# CTRL.net
KiCad netlist of a schematic drawn in Altium Designer
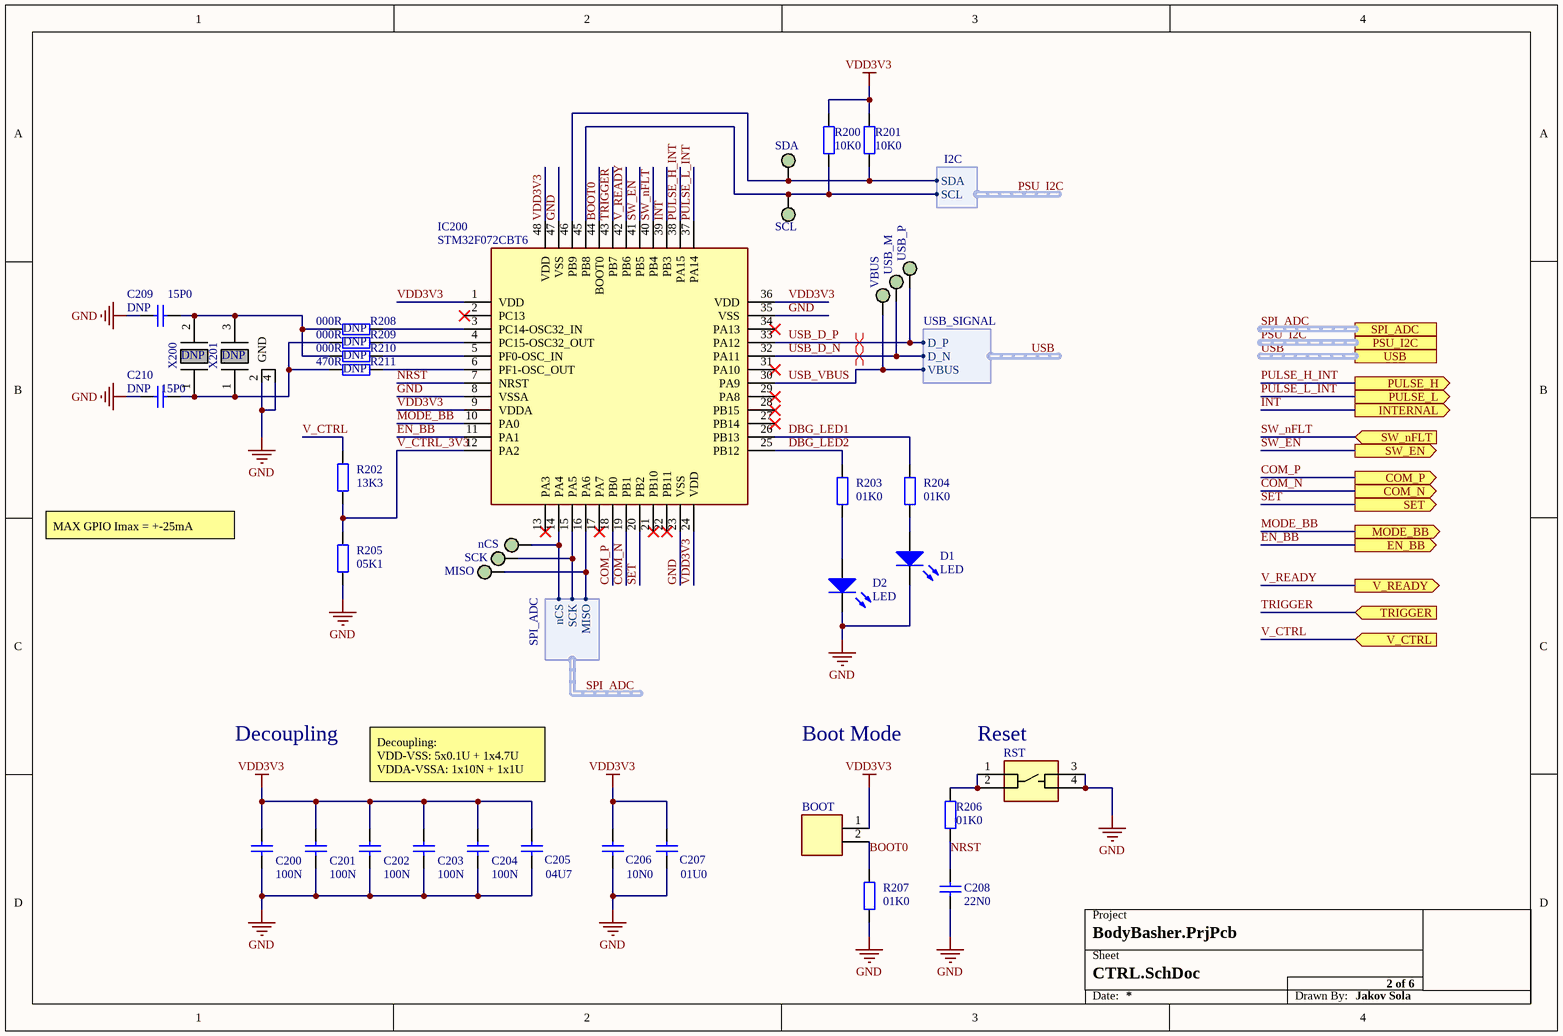
[diagram p0: CTRL.SchDoc]

(export (version "E")
  (design (tool "Eeschema 10.0.6"))
  (components
    (comp (ref "BOOT")
      (value "CON_2P")
      (footprint "2MMHBS02VT02HTB")
      (libsource (lib "Other_passive") (part "CON_2P"))
    )
    (comp (ref "C200")
      (value "Cap")
      (footprint "CAPC0603N")
      (fields
        (field (name "VALUE_4C") "100N")
        (field (name "VOLTAGE") "25V")
        (field (name "TOLERANCE") "0.1")
      )
      (libsource (lib "Capacitors") (part "Cap"))
    )
    (comp (ref "C201")
      (value "Cap")
      (footprint "CAPC0603N")
      (fields
        (field (name "VALUE_4C") "100N")
        (field (name "VOLTAGE") "25V")
        (field (name "TOLERANCE") "0.1")
      )
      (libsource (lib "Capacitors") (part "Cap"))
    )
    (comp (ref "C202")
      (value "Cap")
      (footprint "CAPC0603N")
      (fields
        (field (name "VALUE_4C") "100N")
        (field (name "VOLTAGE") "25V")
        (field (name "TOLERANCE") "0.1")
      )
      (libsource (lib "Capacitors") (part "Cap"))
    )
    (comp (ref "C203")
      (value "Cap")
      (footprint "CAPC0603N")
      (fields
        (field (name "VALUE_4C") "100N")
        (field (name "VOLTAGE") "25V")
        (field (name "TOLERANCE") "0.1")
      )
      (libsource (lib "Capacitors") (part "Cap"))
    )
    (comp (ref "C204")
      (value "Cap")
      (footprint "CAPC0603N")
      (fields
        (field (name "VALUE_4C") "100N")
        (field (name "VOLTAGE") "25V")
        (field (name "TOLERANCE") "0.1")
      )
      (libsource (lib "Capacitors") (part "Cap"))
    )
    (comp (ref "C205")
      (value "Cap")
      (footprint "CAPC1206N")
      (fields
        (field (name "VALUE_4C") "04U7")
        (field (name "VOLTAGE") "50V")
        (field (name "TOLERANCE") "0.1")
      )
      (libsource (lib "Capacitors") (part "Cap"))
    )
    (comp (ref "C206")
      (value "Cap")
      (footprint "CAPC0603N")
      (fields
        (field (name "VALUE_4C") "10N0")
        (field (name "VOLTAGE") "10V")
        (field (name "TOLERANCE") "0.1")
      )
      (libsource (lib "Capacitors") (part "Cap"))
    )
    (comp (ref "C207")
      (value "Cap")
      (footprint "CAPC0603N")
      (fields
        (field (name "VALUE_4C") "01U0")
        (field (name "VOLTAGE") "16V")
        (field (name "TOLERANCE") "0.1")
      )
      (libsource (lib "Capacitors") (part "Cap"))
    )
    (comp (ref "C208")
      (value "Cap")
      (footprint "CAPC0603N")
      (fields
        (field (name "VALUE_4C") "22N0")
        (field (name "VOLTAGE") "10V")
        (field (name "TOLERANCE") "0.1")
      )
      (libsource (lib "Capacitors") (part "Cap"))
    )
    (comp (ref "C209")
      (value "Cap")
      (footprint "CAPC0603N")
      (fields
        (field (name "POPULATE") "DNP")
        (field (name "VALUE_4C") "15P0")
        (field (name "VOLTAGE") "10V")
        (field (name "TOLERANCE") "0.1")
      )
      (libsource (lib "Capacitors") (part "Cap"))
    )
    (comp (ref "C210")
      (value "Cap")
      (footprint "CAPC0603N")
      (fields
        (field (name "POPULATE") "DNP")
        (field (name "VALUE_4C") "15P0")
        (field (name "VOLTAGE") "10V")
        (field (name "TOLERANCE") "0.1")
      )
      (libsource (lib "Capacitors") (part "Cap"))
    )
    (comp (ref "D1") (value "LED") (footprint "LED0603_GREEN") (libsource (lib "Diodes") (part "LED")))
    (comp (ref "D2") (value "LED") (footprint "LED0603_GREEN") (libsource (lib "Diodes") (part "LED")))
    (comp (ref "IC200")
      (value "STM32F0")
      (footprint "LQFP48")
      (fields (field (name "MANUFCODE") "STM32F072CBT6"))
      (libsource (lib "Integrated_circuits") (part "STM32F0"))
    )
    (comp (ref "MISO") (value "TP") (footprint "TP") (libsource (lib "Other_passive") (part "TP")))
    (comp (ref "nCS") (value "TP") (footprint "TP") (libsource (lib "Other_passive") (part "TP")))
    (comp (ref "R200")
      (value "Res")
      (footprint "RESC0603N")
      (description "Resistor")
      (fields (field (name "VALUE_4C") "10K0") (field (name "POWER") "0.1W") (field (name "TOLERANCE") "1%"))
      (libsource (lib "") (part "Res_1"))
    )
    (comp (ref "R201")
      (value "Res")
      (footprint "RESC0603N")
      (description "Resistor")
      (fields (field (name "VALUE_4C") "10K0") (field (name "POWER") "0.1W") (field (name "TOLERANCE") "1%"))
      (libsource (lib "") (part "Res_1"))
    )
    (comp (ref "R202")
      (value "Res")
      (footprint "RESC0603N")
      (description "Resistor")
      (fields (field (name "VALUE_4C") "13K3") (field (name "POWER") "0.1W") (field (name "TOLERANCE") "1%"))
      (libsource (lib "Resistors") (part "Res"))
    )
    (comp (ref "R203")
      (value "Res")
      (footprint "RESC0603N")
      (description "Resistor")
      (fields
        (field (name "VALUE_4C") "01K0")
        (field (name "POWER") "0.063W")
        (field (name "TOLERANCE") "1%")
      )
      (libsource (lib "Resistors") (part "Res"))
    )
    (comp (ref "R204")
      (value "Res")
      (footprint "RESC0603N")
      (description "Resistor")
      (fields
        (field (name "VALUE_4C") "01K0")
        (field (name "POWER") "0.063W")
        (field (name "TOLERANCE") "1%")
      )
      (libsource (lib "Resistors") (part "Res"))
    )
    (comp (ref "R205")
      (value "Res")
      (footprint "RESC0603N")
      (description "Resistor")
      (fields (field (name "VALUE_4C") "05K1") (field (name "POWER") "0.1W") (field (name "TOLERANCE") "1%"))
      (libsource (lib "Resistors") (part "Res"))
    )
    (comp (ref "R206")
      (value "Res")
      (footprint "RESC0603N")
      (description "Resistor")
      (fields
        (field (name "VALUE_4C") "01K0")
        (field (name "POWER") "0.063W")
        (field (name "TOLERANCE") "1%")
      )
      (libsource (lib "Resistors") (part "Res"))
    )
    (comp (ref "R207")
      (value "Res")
      (footprint "RESC0603N")
      (description "Resistor")
      (fields
        (field (name "VALUE_4C") "01K0")
        (field (name "POWER") "0.063W")
        (field (name "TOLERANCE") "1%")
      )
      (libsource (lib "Resistors") (part "Res"))
    )
    (comp (ref "R208")
      (value "Res")
      (footprint "RESC0603N")
      (description "Resistor")
      (fields
        (field (name "POPULATE") "DNP")
        (field (name "VALUE_4C") "000R")
        (field (name "POWER") "0.1W")
        (field (name "TOLERANCE") "1%")
      )
      (libsource (lib "") (part "Res_1"))
    )
    (comp (ref "R209")
      (value "Res")
      (footprint "RESC0603N")
      (description "Resistor")
      (fields
        (field (name "POPULATE") "DNP")
        (field (name "VALUE_4C") "000R")
        (field (name "POWER") "0.1W")
        (field (name "TOLERANCE") "1%")
      )
      (libsource (lib "") (part "Res_1"))
    )
    (comp (ref "R210")
      (value "Res")
      (footprint "RESC0603N")
      (description "Resistor")
      (fields
        (field (name "POPULATE") "DNP")
        (field (name "VALUE_4C") "000R")
        (field (name "POWER") "0.1W")
        (field (name "TOLERANCE") "1%")
      )
      (libsource (lib "") (part "Res_1"))
    )
    (comp (ref "R211")
      (value "Res")
      (footprint "RESC0603N")
      (description "Resistor")
      (fields
        (field (name "POPULATE") "DNP")
        (field (name "VALUE_4C") "470R")
        (field (name "POWER") "0.1W")
        (field (name "TOLERANCE") "0.1%")
      )
      (libsource (lib "") (part "Res_1"))
    )
    (comp (ref "RST")
      (value "4P_BTN")
      (footprint "FSM2J_1")
      (libsource (lib "Other_passive") (part "4P_BTN"))
    )
    (comp (ref "SCK") (value "TP") (footprint "TP") (libsource (lib "Other_passive") (part "TP")))
    (comp (ref "SCL") (value "TP") (footprint "TP") (libsource (lib "Other_passive") (part "TP")))
    (comp (ref "SDA") (value "TP") (footprint "TP") (libsource (lib "Other_passive") (part "TP")))
    (comp (ref "USB_M") (value "TP") (footprint "TP") (libsource (lib "Other_passive") (part "TP")))
    (comp (ref "USB_P") (value "TP") (footprint "TP") (libsource (lib "Other_passive") (part "TP")))
    (comp (ref "VBUS") (value "TP") (footprint "TP") (libsource (lib "Other_passive") (part "TP")))
    (comp (ref "X200")
      (value "CRY_2P")
      (footprint "XTAL_ABS07-32.768KHZ-7-T")
      (fields (field (name "POPULATE") "DNP"))
      (libsource (lib "Other_passive") (part "CRY_2P"))
    )
    (comp (ref "X201")
      (value "CRY_4P")
      (footprint "FC3BAEBDI80T1")
      (fields (field (name "POPULATE") "DNP"))
      (libsource (lib "Other_passive") (part "CRY_4P"))
    )
  )
  (nets
    (net (code "6") (name "/BOOT0") (class "Default")
      (node (ref "BOOT") (pin "2") (pinfunction "2_2") (pintype "passive"))
      (node (ref "IC200") (pin "44") (pinfunction "BOOT0_44") (pintype "passive"))
      (node (ref "R207") (pin "2") (pinfunction "2_2") (pintype "passive"))
    )
    (net (code "7") (name "/COM_N") (class "Default")
      (node (ref "IC200") (pin "19") (pinfunction "PB1_19") (pintype "passive"))
    )
    (net (code "8") (name "/COM_P") (class "Default")
      (node (ref "IC200") (pin "18") (pinfunction "PB0_18") (pintype "passive"))
    )
    (net (code "9") (name "/DBG_LED1") (class "Default")
      (node (ref "IC200") (pin "26") (pinfunction "PB13_26") (pintype "passive"))
      (node (ref "R204") (pin "2") (pinfunction "2_2") (pintype "passive"))
    )
    (net (code "10") (name "/DBG_LED2") (class "Default")
      (node (ref "IC200") (pin "25") (pinfunction "PB12_25") (pintype "passive"))
      (node (ref "R203") (pin "2") (pinfunction "2_2") (pintype "passive"))
    )
    (net (code "11") (name "/EN_BB") (class "Default")
      (node (ref "IC200") (pin "11") (pinfunction "PA1_11") (pintype "passive"))
    )
    (net (code "12") (name "/INT") (class "Default")
      (node (ref "IC200") (pin "39") (pinfunction "PB3_39") (pintype "passive"))
    )
    (net (code "13") (name "/MODE_BB") (class "Default")
      (node (ref "IC200") (pin "10") (pinfunction "PA0_10") (pintype "passive"))
    )
    (net (code "14") (name "/NRST") (class "Default")
      (node (ref "C208") (pin "2") (pinfunction "2_2") (pintype "passive"))
      (node (ref "IC200") (pin "7") (pinfunction "NRST_7") (pintype "passive"))
      (node (ref "R206") (pin "1") (pinfunction "1_1") (pintype "passive"))
    )
    (net (code "16") (name "/PULSE_H_INT") (class "Default")
      (node (ref "IC200") (pin "38") (pinfunction "PA15_38") (pintype "passive"))
    )
    (net (code "17") (name "/PULSE_L_INT") (class "Default")
      (node (ref "IC200") (pin "37") (pinfunction "PA14_37") (pintype "passive"))
    )
    (net (code "18") (name "/SET") (class "Default")
      (node (ref "IC200") (pin "20") (pinfunction "PB2_20") (pintype "passive"))
    )
    (net (code "20") (name "/SW_EN") (class "Default")
      (node (ref "IC200") (pin "41") (pinfunction "PB5_41") (pintype "passive"))
    )
    (net (code "21") (name "/SW_nFLT") (class "Default")
      (node (ref "IC200") (pin "40") (pinfunction "PB4_40") (pintype "passive"))
    )
    (net (code "22") (name "/TRIGGER") (class "Default")
      (node (ref "IC200") (pin "43") (pinfunction "PB7_43") (pintype "passive"))
    )
    (net (code "23") (name "/USB_D_N") (class "Default")
      (node (ref "IC200") (pin "32") (pinfunction "PA11_32") (pintype "passive"))
      (node (ref "USB_M") (pin "TP") (pinfunction "TP_TP") (pintype "passive"))
    )
    (net (code "24") (name "/USB_D_P") (class "Default")
      (node (ref "IC200") (pin "33") (pinfunction "PA12_33") (pintype "passive"))
      (node (ref "USB_P") (pin "TP") (pinfunction "TP_TP") (pintype "passive"))
    )
    (net (code "25") (name "/USB_VBUS") (class "Default")
      (node (ref "IC200") (pin "30") (pinfunction "PA9_30") (pintype "passive"))
      (node (ref "VBUS") (pin "TP") (pinfunction "TP_TP") (pintype "passive"))
    )
    (net (code "27") (name "/V_CTRL") (class "Default")
      (node (ref "R202") (pin "2") (pinfunction "2_2") (pintype "passive"))
    )
    (net (code "28") (name "/V_CTRL_3V3") (class "Default")
      (node (ref "IC200") (pin "12") (pinfunction "PA2_12") (pintype "passive"))
      (node (ref "R202") (pin "1") (pinfunction "1_1") (pintype "passive"))
      (node (ref "R205") (pin "2") (pinfunction "2_2") (pintype "passive"))
    )
    (net (code "29") (name "/V_READY") (class "Default")
      (node (ref "IC200") (pin "42") (pinfunction "PB6_42") (pintype "passive"))
    )
    (net (code "30") (name "GND") (class "Default")
      (node (ref "C200") (pin "1") (pinfunction "1_1") (pintype "passive"))
      (node (ref "C201") (pin "1") (pinfunction "1_1") (pintype "passive"))
      (node (ref "C202") (pin "1") (pinfunction "1_1") (pintype "passive"))
      (node (ref "C203") (pin "1") (pinfunction "1_1") (pintype "passive"))
      (node (ref "C204") (pin "1") (pinfunction "1_1") (pintype "passive"))
      (node (ref "C205") (pin "1") (pinfunction "1_1") (pintype "passive"))
      (node (ref "C206") (pin "1") (pinfunction "1_1") (pintype "passive"))
      (node (ref "C207") (pin "1") (pinfunction "1_1") (pintype "passive"))
      (node (ref "C208") (pin "1") (pinfunction "1_1") (pintype "passive"))
      (node (ref "C209") (pin "1") (pinfunction "1_1") (pintype "passive"))
      (node (ref "C210") (pin "1") (pinfunction "1_1") (pintype "passive"))
      (node (ref "D1") (pin "2") (pinfunction "K_2") (pintype "passive"))
      (node (ref "D2") (pin "2") (pinfunction "K_2") (pintype "passive"))
      (node (ref "IC200") (pin "23") (pinfunction "VSS_23") (pintype "passive"))
      (node (ref "IC200") (pin "35") (pinfunction "VSS_35") (pintype "passive"))
      (node (ref "IC200") (pin "47") (pinfunction "VSS_47") (pintype "passive"))
      (node (ref "IC200") (pin "8") (pinfunction "VSSA_8") (pintype "passive"))
      (node (ref "R205") (pin "1") (pinfunction "1_1") (pintype "passive"))
      (node (ref "R207") (pin "1") (pinfunction "1_1") (pintype "passive"))
      (node (ref "RST") (pin "3") (pinfunction "3_3") (pintype "passive"))
      (node (ref "RST") (pin "4") (pinfunction "4_4") (pintype "passive"))
      (node (ref "X201") (pin "2") (pinfunction "GND_2") (pintype "passive"))
      (node (ref "X201") (pin "4") (pinfunction "GND_4") (pintype "passive"))
    )
    (net (code "31") (name "Net-(D1-A)") (class "Default")
      (node (ref "D1") (pin "1") (pinfunction "A_1") (pintype "passive"))
      (node (ref "R204") (pin "1") (pinfunction "1_1") (pintype "passive"))
    )
    (net (code "32") (name "Net-(D2-A)") (class "Default")
      (node (ref "D2") (pin "1") (pinfunction "A_1") (pintype "passive"))
      (node (ref "R203") (pin "1") (pinfunction "1_1") (pintype "passive"))
    )
    (net (code "33") (name "Net-(IC200-PA4)") (class "Default")
      (node (ref "IC200") (pin "14") (pinfunction "PA4_14") (pintype "passive"))
      (node (ref "nCS") (pin "TP") (pinfunction "TP_TP") (pintype "passive"))
    )
    (net (code "34") (name "Net-(IC200-PA5)") (class "Default")
      (node (ref "IC200") (pin "15") (pinfunction "PA5_15") (pintype "passive"))
      (node (ref "SCK") (pin "TP") (pinfunction "TP_TP") (pintype "passive"))
    )
    (net (code "35") (name "Net-(IC200-PA6)") (class "Default")
      (node (ref "IC200") (pin "16") (pinfunction "PA6_16") (pintype "passive"))
      (node (ref "MISO") (pin "TP") (pinfunction "TP_TP") (pintype "passive"))
    )
    (net (code "36") (name "Net-(IC200-PB8)") (class "Default")
      (node (ref "IC200") (pin "45") (pinfunction "PB8_45") (pintype "passive"))
      (node (ref "R200") (pin "1") (pinfunction "1_1") (pintype "passive"))
      (node (ref "SCL") (pin "TP") (pinfunction "TP_TP") (pintype "passive"))
    )
    (net (code "37") (name "Net-(IC200-PB9)") (class "Default")
      (node (ref "IC200") (pin "46") (pinfunction "PB9_46") (pintype "passive"))
      (node (ref "R201") (pin "1") (pinfunction "1_1") (pintype "passive"))
      (node (ref "SDA") (pin "TP") (pinfunction "TP_TP") (pintype "passive"))
    )
    (net (code "38") (name "Net-(IC200-PC14-OSC32_IN)") (class "Default")
      (node (ref "IC200") (pin "3") (pinfunction "PC14-OSC32_IN_3") (pintype "passive"))
      (node (ref "R208") (pin "2") (pinfunction "2_2") (pintype "passive"))
    )
    (net (code "39") (name "Net-(IC200-PC15-OSC32_OUT)") (class "Default")
      (node (ref "IC200") (pin "4") (pinfunction "PC15-OSC32_OUT_4") (pintype "passive"))
      (node (ref "R209") (pin "2") (pinfunction "2_2") (pintype "passive"))
    )
    (net (code "40") (name "Net-(IC200-PF0-OSC_IN)") (class "Default")
      (node (ref "IC200") (pin "5") (pinfunction "PF0-OSC_IN_5") (pintype "passive"))
      (node (ref "R210") (pin "2") (pinfunction "2_2") (pintype "passive"))
    )
    (net (code "41") (name "Net-(IC200-PF1-OSC_OUT)") (class "Default")
      (node (ref "IC200") (pin "6") (pinfunction "PF1-OSC_OUT_6") (pintype "passive"))
      (node (ref "R211") (pin "2") (pinfunction "2_2") (pintype "passive"))
    )
    (net (code "42") (name "Net-(R206-Pad2)") (class "Default")
      (node (ref "R206") (pin "2") (pinfunction "2_2") (pintype "passive"))
      (node (ref "RST") (pin "1") (pinfunction "1_1") (pintype "passive"))
      (node (ref "RST") (pin "2") (pinfunction "2_2") (pintype "passive"))
    )
    (net (code "43") (name "Net-(X200-CRYSTAL_1)") (class "Default")
      (node (ref "C210") (pin "2") (pinfunction "2_2") (pintype "passive"))
      (node (ref "R209") (pin "1") (pinfunction "1_1") (pintype "passive"))
      (node (ref "R211") (pin "1") (pinfunction "1_1") (pintype "passive"))
      (node (ref "X200") (pin "1") (pinfunction "CRYSTAL_1_1") (pintype "passive"))
      (node (ref "X201") (pin "1") (pinfunction "CRYSTAL_1_1") (pintype "passive"))
    )
    (net (code "44") (name "Net-(X200-CRYSTAL_2)") (class "Default")
      (node (ref "C209") (pin "2") (pinfunction "2_2") (pintype "passive"))
      (node (ref "R208") (pin "1") (pinfunction "1_1") (pintype "passive"))
      (node (ref "R210") (pin "1") (pinfunction "1_1") (pintype "passive"))
      (node (ref "X200") (pin "2") (pinfunction "CRYSTAL_2_2") (pintype "passive"))
      (node (ref "X201") (pin "3") (pinfunction "CRYSTAL_2_3") (pintype "passive"))
    )
    (net (code "45") (name "VDD3V3") (class "Default")
      (node (ref "BOOT") (pin "1") (pinfunction "1_1") (pintype "passive"))
      (node (ref "C200") (pin "2") (pinfunction "2_2") (pintype "passive"))
      (node (ref "C201") (pin "2") (pinfunction "2_2") (pintype "passive"))
      (node (ref "C202") (pin "2") (pinfunction "2_2") (pintype "passive"))
      (node (ref "C203") (pin "2") (pinfunction "2_2") (pintype "passive"))
      (node (ref "C204") (pin "2") (pinfunction "2_2") (pintype "passive"))
      (node (ref "C205") (pin "2") (pinfunction "2_2") (pintype "passive"))
      (node (ref "C206") (pin "2") (pinfunction "2_2") (pintype "passive"))
      (node (ref "C207") (pin "2") (pinfunction "2_2") (pintype "passive"))
      (node (ref "IC200") (pin "1") (pinfunction "VDD_1") (pintype "passive"))
      (node (ref "IC200") (pin "24") (pinfunction "VDD_24") (pintype "passive"))
      (node (ref "IC200") (pin "36") (pinfunction "VDD_36") (pintype "passive"))
      (node (ref "IC200") (pin "48") (pinfunction "VDD_48") (pintype "passive"))
      (node (ref "IC200") (pin "9") (pinfunction "VDDA_9") (pintype "passive"))
      (node (ref "R200") (pin "2") (pinfunction "2_2") (pintype "passive"))
      (node (ref "R201") (pin "2") (pinfunction "2_2") (pintype "passive"))
    )
    (net (code "46") (name "unconnected-(IC200-PA3-Pad13)") (class "Default")
      (node (ref "IC200") (pin "13") (pinfunction "PA3_13") (pintype "passive+no_connect"))
    )
    (net (code "47") (name "unconnected-(IC200-PA7-Pad17)") (class "Default")
      (node (ref "IC200") (pin "17") (pinfunction "PA7_17") (pintype "passive+no_connect"))
    )
    (net (code "48") (name "unconnected-(IC200-PA8-Pad29)") (class "Default")
      (node (ref "IC200") (pin "29") (pinfunction "PA8_29") (pintype "passive+no_connect"))
    )
    (net (code "49") (name "unconnected-(IC200-PA10-Pad31)") (class "Default")
      (node (ref "IC200") (pin "31") (pinfunction "PA10_31") (pintype "passive+no_connect"))
    )
    (net (code "50") (name "unconnected-(IC200-PA13-Pad34)") (class "Default")
      (node (ref "IC200") (pin "34") (pinfunction "PA13_34") (pintype "passive+no_connect"))
    )
    (net (code "51") (name "unconnected-(IC200-PB10-Pad21)") (class "Default")
      (node (ref "IC200") (pin "21") (pinfunction "PB10_21") (pintype "passive+no_connect"))
    )
    (net (code "52") (name "unconnected-(IC200-PB11-Pad22)") (class "Default")
      (node (ref "IC200") (pin "22") (pinfunction "PB11_22") (pintype "passive+no_connect"))
    )
    (net (code "53") (name "unconnected-(IC200-PB14-Pad27)") (class "Default")
      (node (ref "IC200") (pin "27") (pinfunction "PB14_27") (pintype "passive+no_connect"))
    )
    (net (code "54") (name "unconnected-(IC200-PB15-Pad28)") (class "Default")
      (node (ref "IC200") (pin "28") (pinfunction "PB15_28") (pintype "passive+no_connect"))
    )
    (net (code "55") (name "unconnected-(IC200-PC13-Pad2)") (class "Default")
      (node (ref "IC200") (pin "2") (pinfunction "PC13_2") (pintype "passive+no_connect"))
    )
  )
)
